# LTC6241CS8PBF_breakout.net
KiCad netlist of a schematic drawn in EAGLE
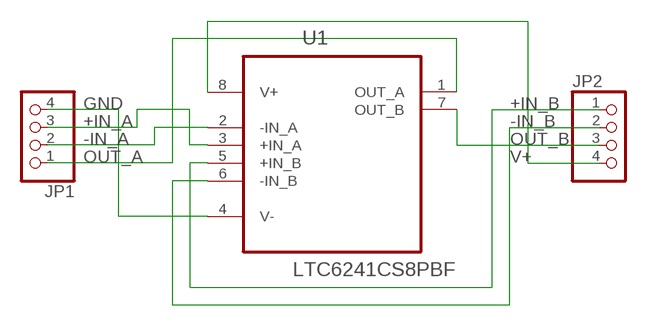
[diagram p0: schematic, sheet 1]

(export (version "E")
  (design (tool "Eeschema 10.0.6"))
  (components
    (comp (ref "JP1")
      (value "PINHD-1X4")
      (footprint "eagle-import:1X04")
      (libsource (lib "eagle-import") (part "PINHD-1X4"))
    )
    (comp (ref "JP2")
      (value "PINHD-1X4")
      (footprint "eagle-import:1X04")
      (libsource (lib "eagle-import") (part "PINHD-1X4"))
    )
    (comp (ref "U1")
      (value "LTC6241CS8PBF")
      (footprint "eagle-import:SOIC127P600X175-8N")
      (fields (field (name "MF") "Linear Technology") (field (name "MP") "LTC6241CS8#PBF"))
      (libsource (lib "eagle-import") (part "LTC6241CS8PBF"))
    )
  )
  (nets
    (net (code "1") (name "/+IN_A") (class "Default")
      (node (ref "JP1") (pin "3") (pinfunction "3_3") (pintype "passive"))
      (node (ref "U1") (pin "3") (pinfunction "+IN_A_3") (pintype "input"))
    )
    (net (code "2") (name "/+IN_B") (class "Default")
      (node (ref "JP2") (pin "1") (pinfunction "1_1") (pintype "passive"))
      (node (ref "U1") (pin "5") (pinfunction "+IN_B_5") (pintype "input"))
    )
    (net (code "3") (name "/-IN_A") (class "Default")
      (node (ref "JP1") (pin "2") (pinfunction "2_2") (pintype "passive"))
      (node (ref "U1") (pin "2") (pinfunction "-IN_A_2") (pintype "input"))
    )
    (net (code "4") (name "/-IN_B") (class "Default")
      (node (ref "JP2") (pin "2") (pinfunction "2_2") (pintype "passive"))
      (node (ref "U1") (pin "6") (pinfunction "-IN_B_6") (pintype "input"))
    )
    (net (code "5") (name "/GND") (class "Default")
      (node (ref "JP1") (pin "4") (pinfunction "4_4") (pintype "passive"))
      (node (ref "U1") (pin "4") (pinfunction "V-_4") (pintype "power_in"))
    )
    (net (code "6") (name "/OUT_A") (class "Default")
      (node (ref "JP1") (pin "1") (pinfunction "1_1") (pintype "passive"))
      (node (ref "U1") (pin "1") (pinfunction "OUT_A_1") (pintype "output"))
    )
    (net (code "7") (name "/OUT_B") (class "Default")
      (node (ref "JP2") (pin "3") (pinfunction "3_3") (pintype "passive"))
      (node (ref "U1") (pin "7") (pinfunction "OUT_B_7") (pintype "output"))
    )
    (net (code "8") (name "/V+") (class "Default")
      (node (ref "JP2") (pin "4") (pinfunction "4_4") (pintype "passive"))
      (node (ref "U1") (pin "8") (pinfunction "V+_8") (pintype "power_in"))
    )
  )
)
